# Sensact_v4_2.net
KiCad netlist of a schematic drawn in EAGLE
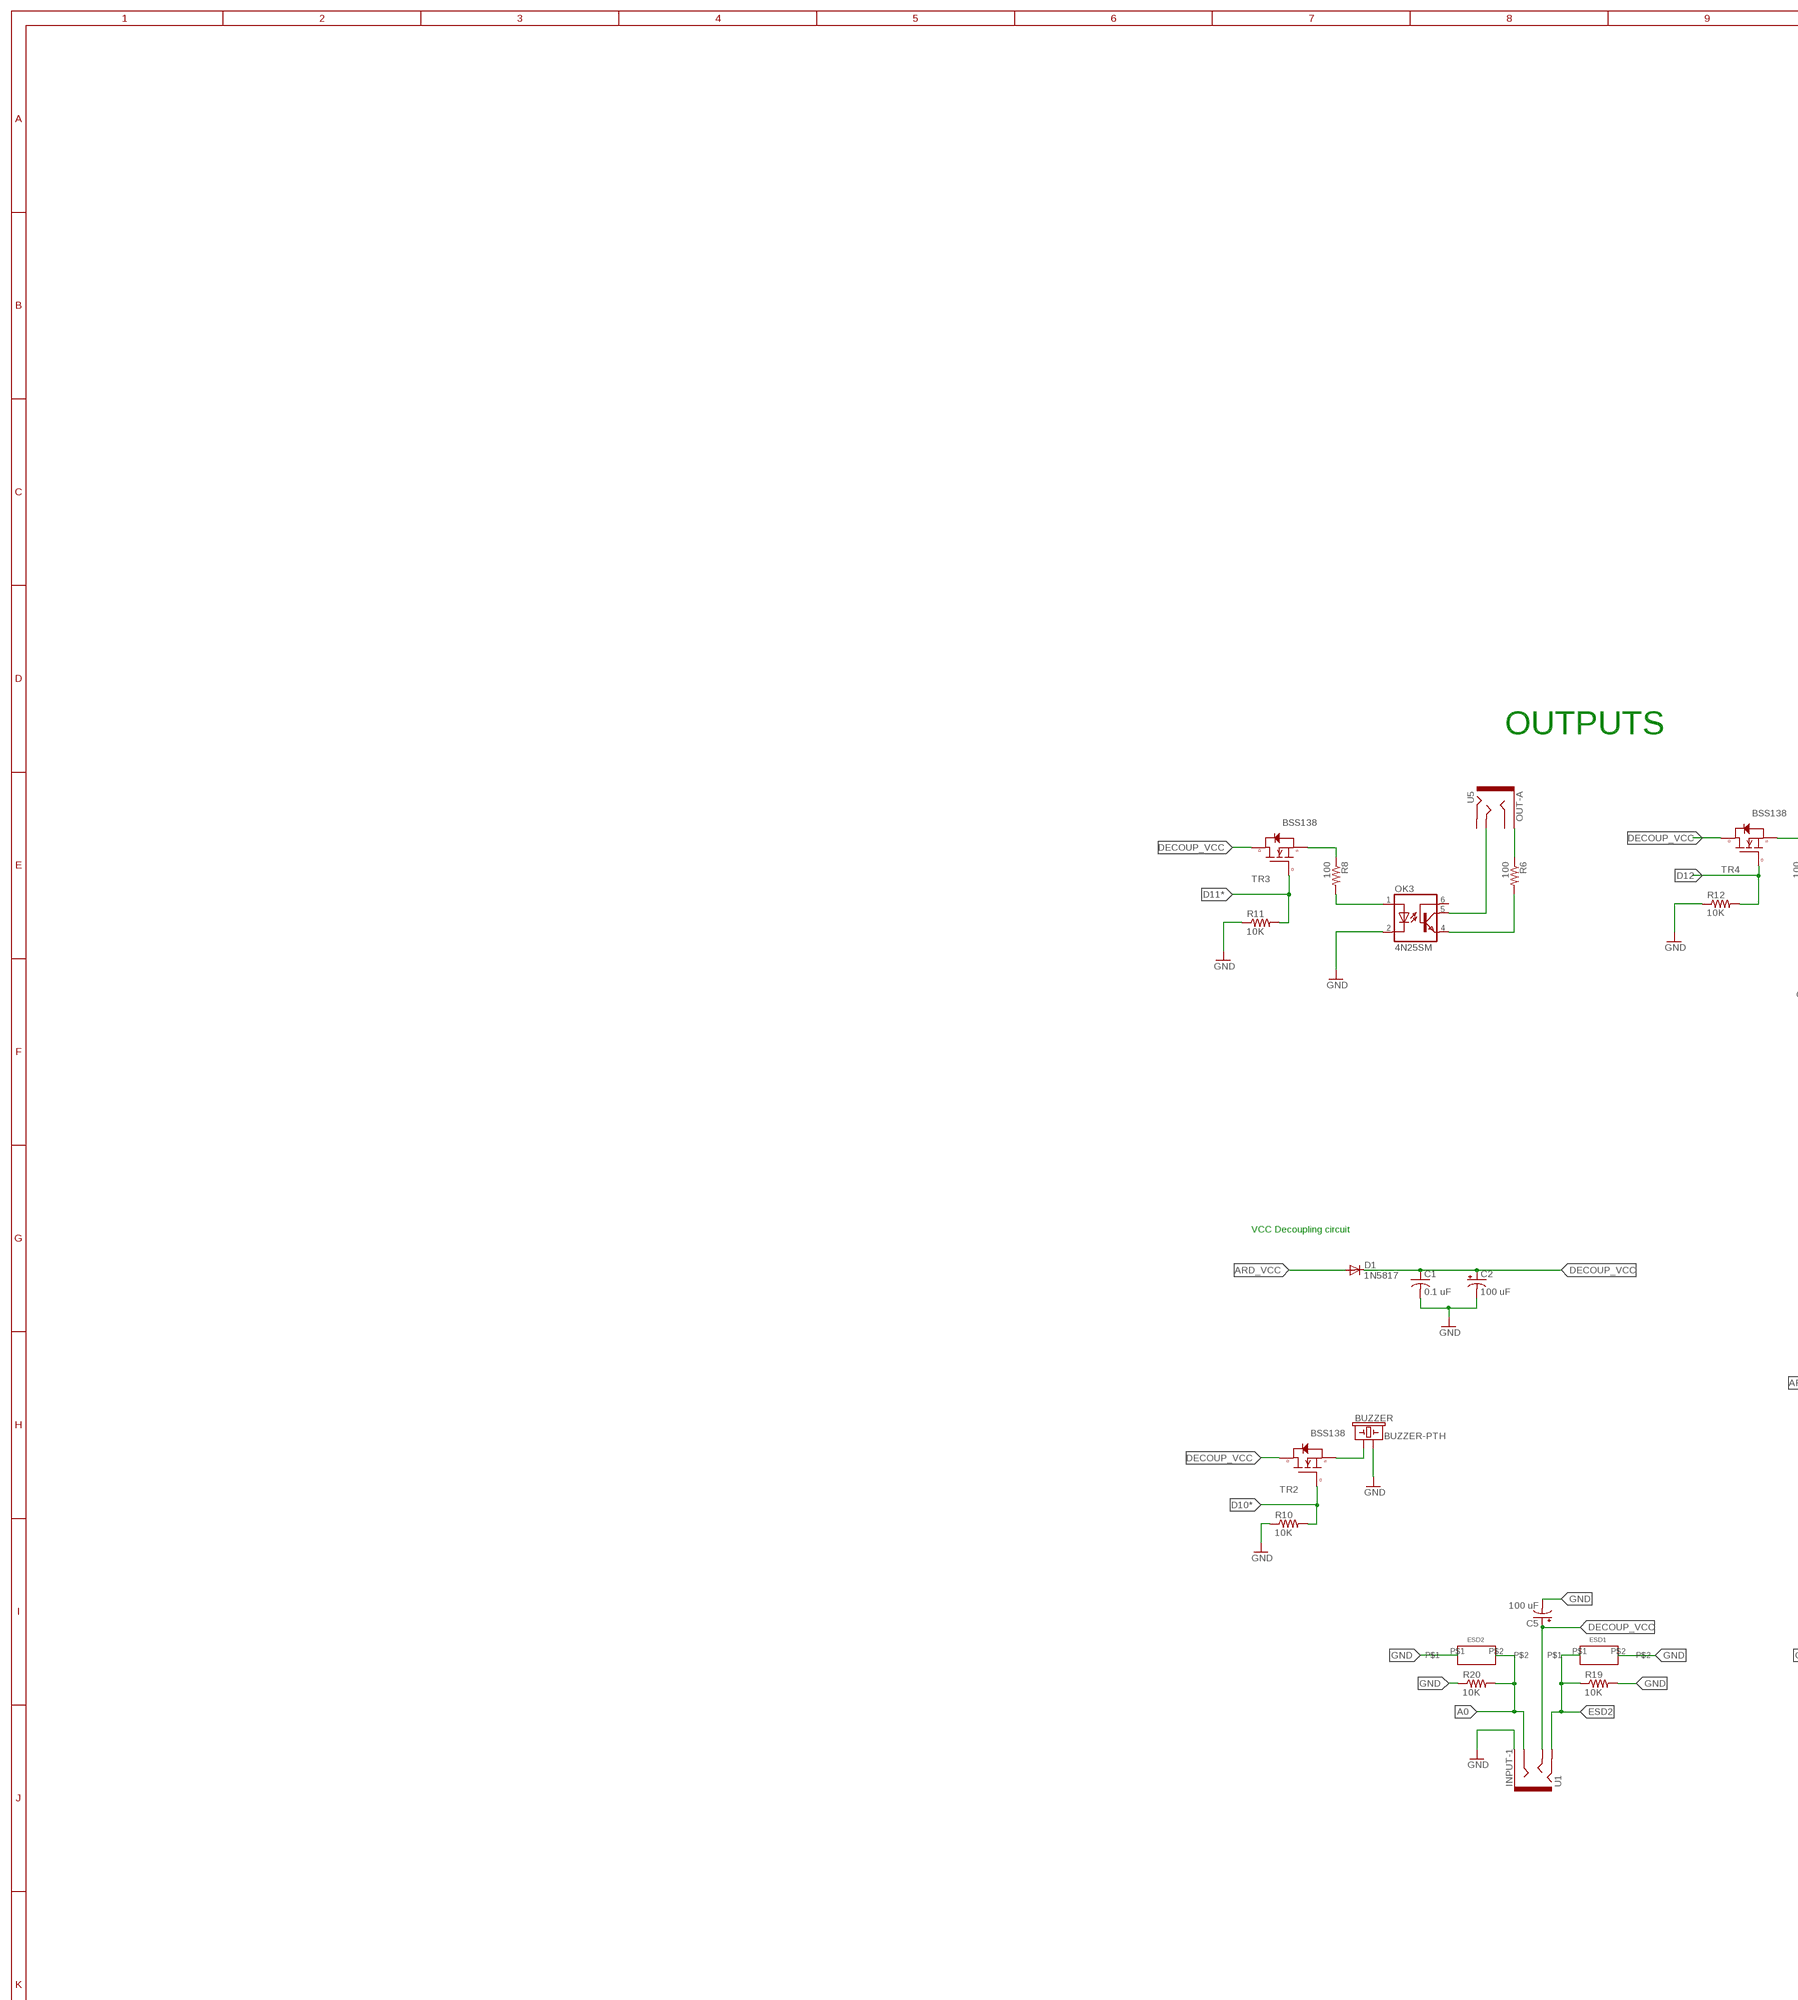
[diagram p0: schematic, sheet 1, part 1 of 3]
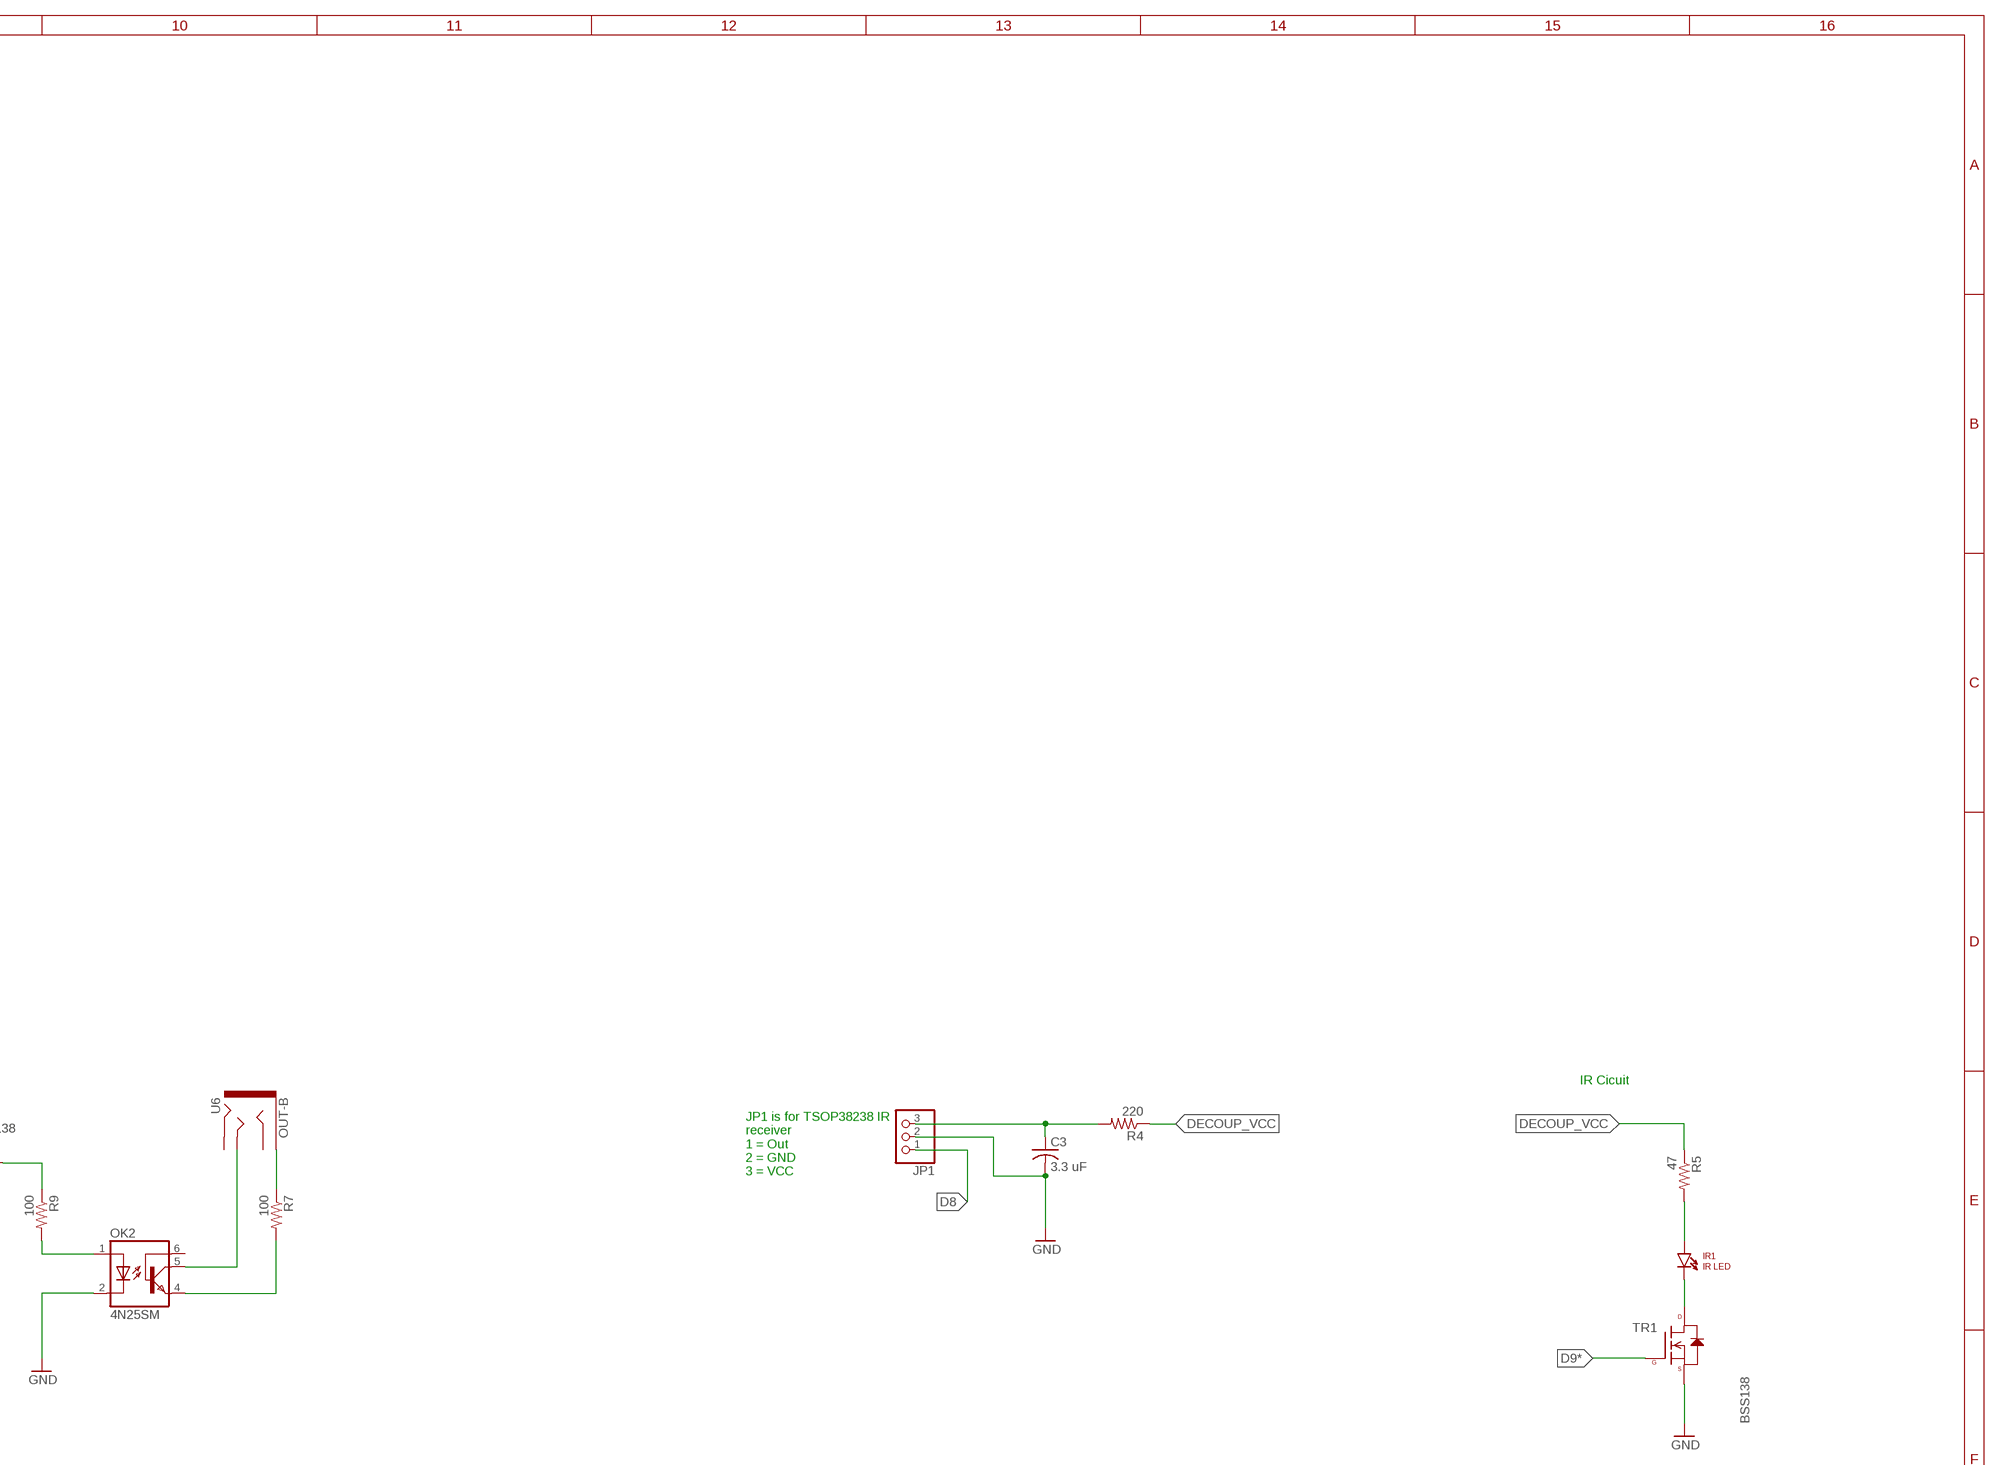
[diagram p1: schematic, sheet 1, part 2 of 3]
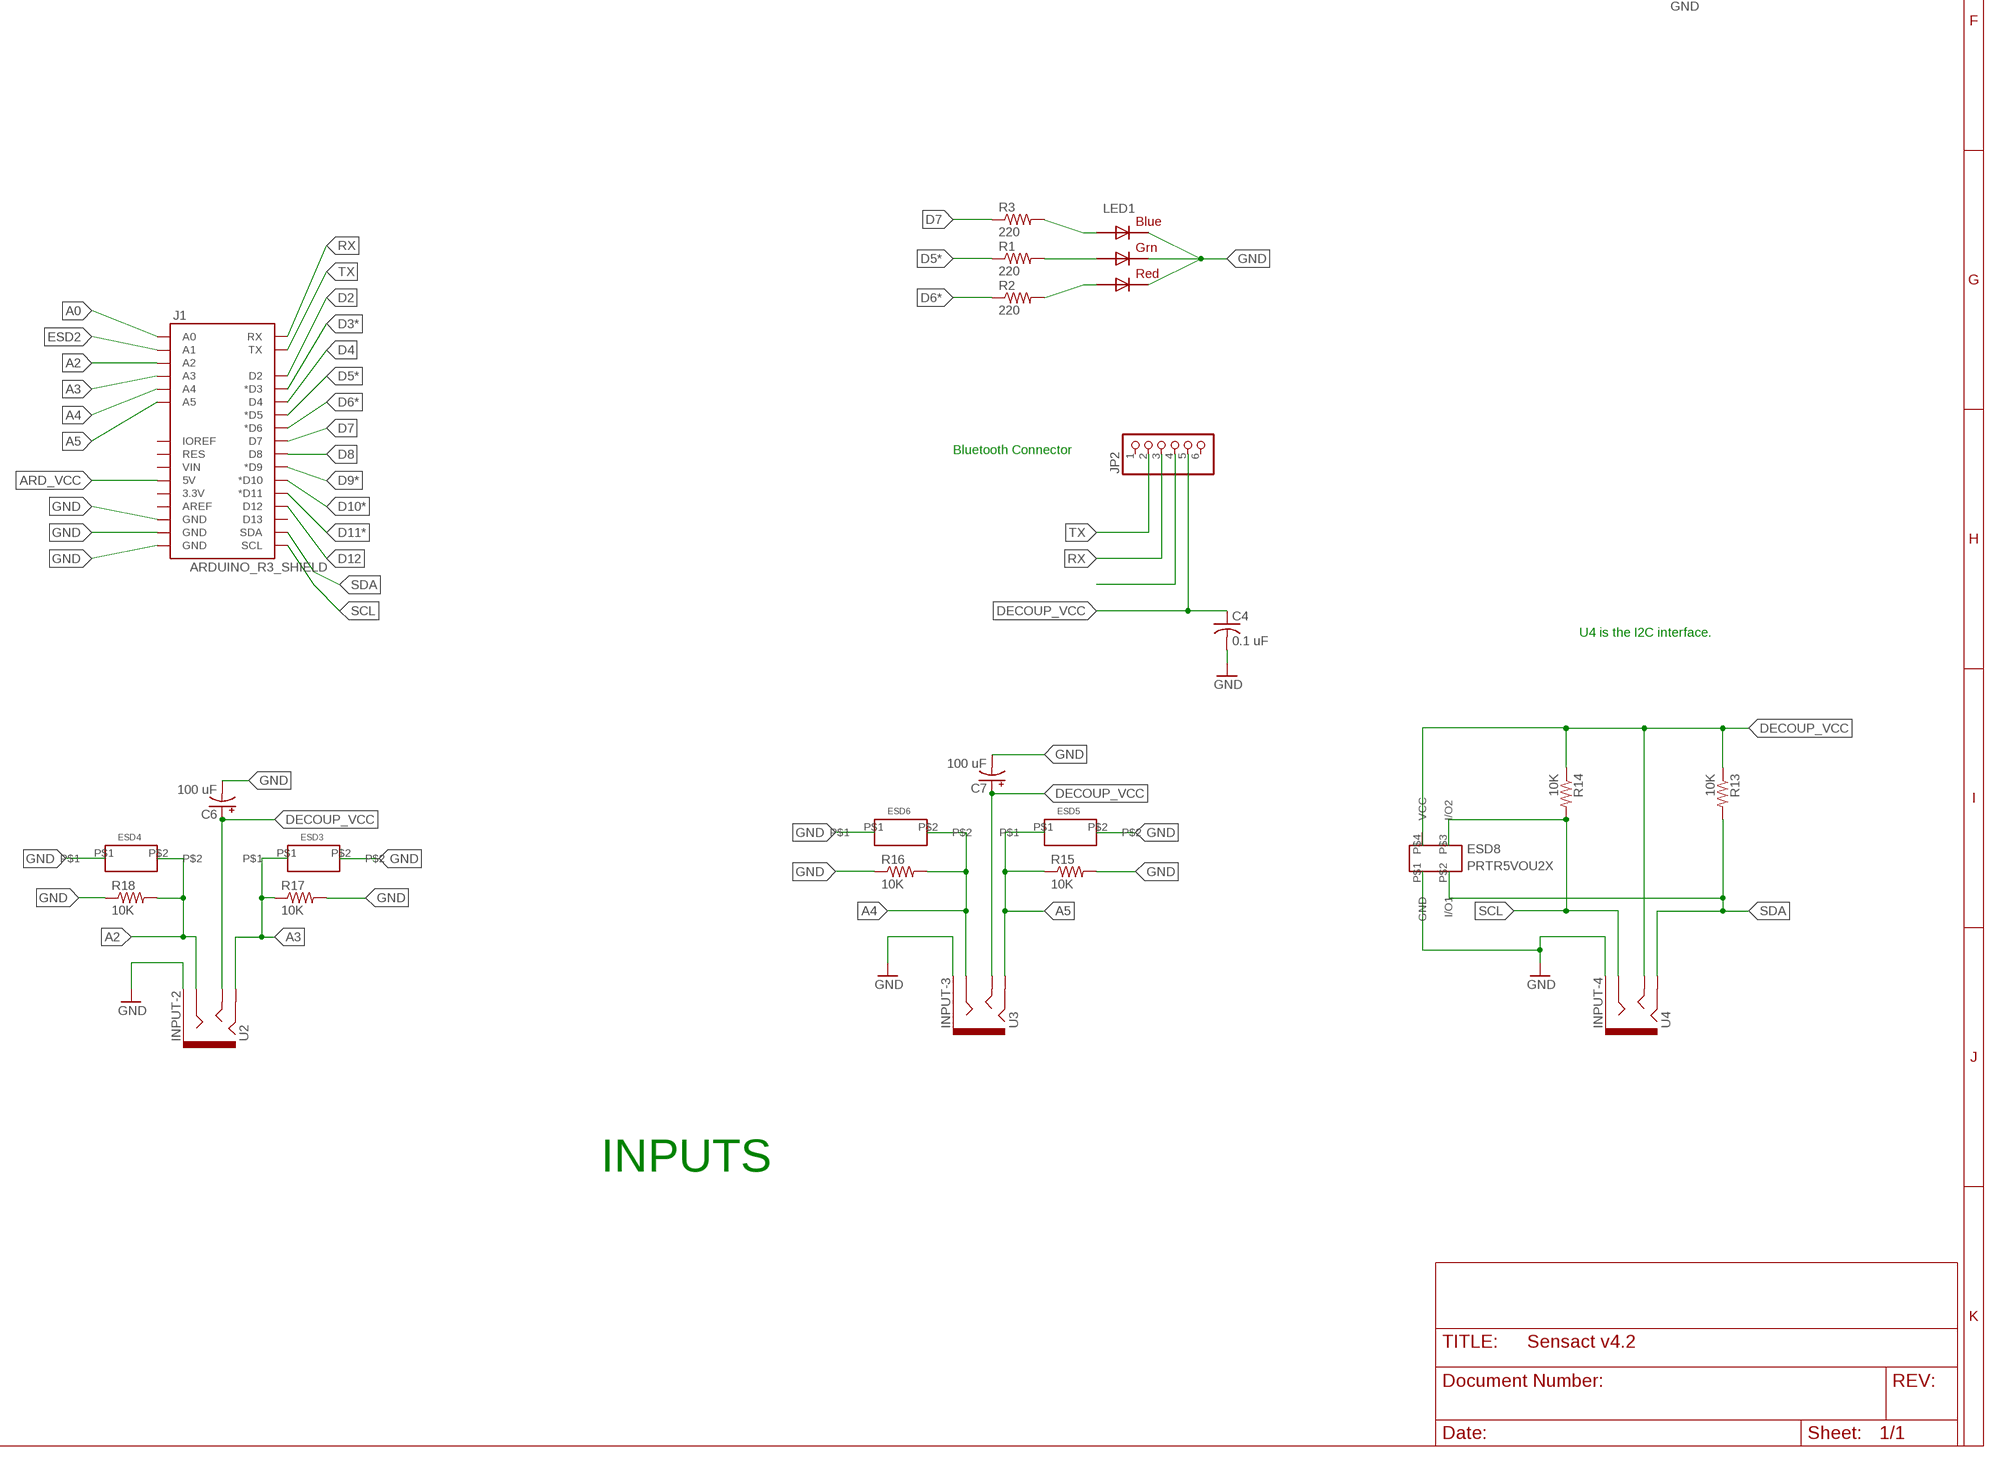
[diagram p2: schematic, sheet 1, part 3 of 3]

(export (version "E")
  (design (tool "Eeschema 10.0.6"))
  (components
    (comp (ref "BUZZER")
      (value "BUZZER-PTH")
      (footprint "eagle-import:BUZZER-12MM")
      (libsource (lib "eagle-import") (part "BUZZER-PTH"))
    )
    (comp (ref "C1")
      (value "0.1 uF")
      (footprint "eagle-import:C0805")
      (libsource (lib "eagle-import") (part "C-USC0805"))
    )
    (comp (ref "C2")
      (value "100 uF")
      (footprint "eagle-import:PANASONIC_C")
      (libsource (lib "eagle-import") (part "CAP_POLC"))
    )
    (comp (ref "C3")
      (value "3.3 uF")
      (footprint "eagle-import:C0805")
      (libsource (lib "eagle-import") (part "C-USC0805"))
    )
    (comp (ref "C4")
      (value "0.1 uF")
      (footprint "eagle-import:C0805")
      (libsource (lib "eagle-import") (part "C-USC0805"))
    )
    (comp (ref "C5")
      (value "100 uF")
      (footprint "eagle-import:PANASONIC_C")
      (libsource (lib "eagle-import") (part "CAP_POLC"))
    )
    (comp (ref "C6")
      (value "100 uF")
      (footprint "eagle-import:PANASONIC_C")
      (libsource (lib "eagle-import") (part "CAP_POLC"))
    )
    (comp (ref "C7")
      (value "100 uF")
      (footprint "eagle-import:PANASONIC_C")
      (libsource (lib "eagle-import") (part "CAP_POLC"))
    )
    (comp (ref "D1")
      (value "1N5817")
      (footprint "eagle-import:DO214AC")
      (libsource (lib "eagle-import") (part "DIODE-DO214AC"))
    )
    (comp (ref "ESD1")
      (value "PESD5V0S1BA")
      (footprint "eagle-import:SOD323")
      (libsource (lib "eagle-import") (part "PESD5V0S1BA"))
    )
    (comp (ref "ESD2")
      (value "PESD5V0S1BA")
      (footprint "eagle-import:SOD323")
      (libsource (lib "eagle-import") (part "PESD5V0S1BA"))
    )
    (comp (ref "ESD3")
      (value "PESD5V0S1BA")
      (footprint "eagle-import:SOD323")
      (libsource (lib "eagle-import") (part "PESD5V0S1BA"))
    )
    (comp (ref "ESD4")
      (value "PESD5V0S1BA")
      (footprint "eagle-import:SOD323")
      (libsource (lib "eagle-import") (part "PESD5V0S1BA"))
    )
    (comp (ref "ESD5")
      (value "PESD5V0S1BA")
      (footprint "eagle-import:SOD323")
      (libsource (lib "eagle-import") (part "PESD5V0S1BA"))
    )
    (comp (ref "ESD6")
      (value "PESD5V0S1BA")
      (footprint "eagle-import:SOD323")
      (libsource (lib "eagle-import") (part "PESD5V0S1BA"))
    )
    (comp (ref "ESD8")
      (value "PRTR5VOU2X")
      (footprint "eagle-import:215")
      (libsource (lib "eagle-import") (part "PRTR5VOU2X"))
    )
    (comp (ref "INPUT-1")
      (value "U1")
      (footprint "eagle-import:AUDIO-JACK-TRRS-THRUHOLE")
      (libsource (lib "eagle-import") (part "AUDIO-JACK-TRRS-THRUHOLE"))
    )
    (comp (ref "INPUT-2")
      (value "U2")
      (footprint "eagle-import:AUDIO-JACK-TRRS-THRUHOLE")
      (libsource (lib "eagle-import") (part "AUDIO-JACK-TRRS-THRUHOLE"))
    )
    (comp (ref "INPUT-3")
      (value "U3")
      (footprint "eagle-import:AUDIO-JACK-TRRS-THRUHOLE")
      (libsource (lib "eagle-import") (part "AUDIO-JACK-TRRS-THRUHOLE"))
    )
    (comp (ref "INPUT-4")
      (value "U4")
      (footprint "eagle-import:AUDIO-JACK-TRRS-THRUHOLE")
      (libsource (lib "eagle-import") (part "AUDIO-JACK-TRRS-THRUHOLE"))
    )
    (comp (ref "IR1")
      (value "IR LED")
      (footprint "eagle-import:LTE-302")
      (libsource (lib "eagle-import") (part "LTE-302"))
    )
    (comp (ref "J1")
      (value "ARDUINO_R3_SHIELD")
      (footprint "eagle-import:UNO_R3_SHIELD")
      (libsource (lib "eagle-import") (part "ARDUINO_R3_SHIELD"))
    )
    (comp (ref "JP1")
      (value "PINHD-1X3")
      (footprint "eagle-import:1X03")
      (libsource (lib "eagle-import") (part "PINHD-1X3"))
    )
    (comp (ref "JP2")
      (value "PINHD-1X6")
      (footprint "eagle-import:1X06")
      (libsource (lib "eagle-import") (part "PINHD-1X6"))
    )
    (comp (ref "LED1")
      (value "RGBLED5050")
      (footprint "eagle-import:RGBLED5050")
      (libsource (lib "eagle-import") (part "RGBLED5050"))
    )
    (comp (ref "OK2")
      (value "4N25SM")
      (footprint "eagle-import:DIL6-SMD")
      (fields (field (name "MF") "FAIRCHILD SEMICONDUCTOR"))
      (libsource (lib "eagle-import") (part "4N?MS25"))
    )
    (comp (ref "OK3")
      (value "4N25SM")
      (footprint "eagle-import:DIL6-SMD")
      (fields (field (name "MF") "FAIRCHILD SEMICONDUCTOR"))
      (libsource (lib "eagle-import") (part "4N?MS25"))
    )
    (comp (ref "OUT-A")
      (value "U5")
      (footprint "eagle-import:AUDIO-JACK-TRRS-THRUHOLE")
      (libsource (lib "eagle-import") (part "AUDIO-JACK-TRRS-THRUHOLE"))
    )
    (comp (ref "OUT-B")
      (value "U6")
      (footprint "eagle-import:AUDIO-JACK-TRRS-THRUHOLE")
      (libsource (lib "eagle-import") (part "AUDIO-JACK-TRRS-THRUHOLE"))
    )
    (comp (ref "R1")
      (value "220")
      (footprint "eagle-import:0805")
      (libsource (lib "eagle-import") (part "RESISTOR0805-RES"))
    )
    (comp (ref "R2")
      (value "220")
      (footprint "eagle-import:0805")
      (libsource (lib "eagle-import") (part "RESISTOR0805-RES"))
    )
    (comp (ref "R3")
      (value "220")
      (footprint "eagle-import:0805")
      (libsource (lib "eagle-import") (part "RESISTOR0805-RES"))
    )
    (comp (ref "R4")
      (value "220")
      (footprint "eagle-import:0805")
      (libsource (lib "eagle-import") (part "RESISTOR0805-RES"))
    )
    (comp (ref "R5")
      (value "47")
      (footprint "eagle-import:0805")
      (libsource (lib "eagle-import") (part "RESISTOR0805-RES"))
    )
    (comp (ref "R6")
      (value "100")
      (footprint "eagle-import:0805")
      (libsource (lib "eagle-import") (part "RESISTOR0805-RES"))
    )
    (comp (ref "R7")
      (value "100")
      (footprint "eagle-import:0805")
      (libsource (lib "eagle-import") (part "RESISTOR0805-RES"))
    )
    (comp (ref "R8")
      (value "100")
      (footprint "eagle-import:0805")
      (libsource (lib "eagle-import") (part "RESISTOR0805-RES"))
    )
    (comp (ref "R9")
      (value "100")
      (footprint "eagle-import:0805")
      (libsource (lib "eagle-import") (part "RESISTOR0805-RES"))
    )
    (comp (ref "R10")
      (value "10K")
      (footprint "eagle-import:0805")
      (libsource (lib "eagle-import") (part "RESISTOR0805-RES"))
    )
    (comp (ref "R11")
      (value "10K")
      (footprint "eagle-import:0805")
      (libsource (lib "eagle-import") (part "RESISTOR0805-RES"))
    )
    (comp (ref "R12")
      (value "10K")
      (footprint "eagle-import:0805")
      (libsource (lib "eagle-import") (part "RESISTOR0805-RES"))
    )
    (comp (ref "R13")
      (value "10K")
      (footprint "eagle-import:0805")
      (libsource (lib "eagle-import") (part "RESISTOR0805-RES"))
    )
    (comp (ref "R14")
      (value "10K")
      (footprint "eagle-import:0805")
      (libsource (lib "eagle-import") (part "RESISTOR0805-RES"))
    )
    (comp (ref "R15")
      (value "10K")
      (footprint "eagle-import:0805")
      (libsource (lib "eagle-import") (part "RESISTOR0805-RES"))
    )
    (comp (ref "R16")
      (value "10K")
      (footprint "eagle-import:0805")
      (libsource (lib "eagle-import") (part "RESISTOR0805-RES"))
    )
    (comp (ref "R17")
      (value "10K")
      (footprint "eagle-import:0805")
      (libsource (lib "eagle-import") (part "RESISTOR0805-RES"))
    )
    (comp (ref "R18")
      (value "10K")
      (footprint "eagle-import:0805")
      (libsource (lib "eagle-import") (part "RESISTOR0805-RES"))
    )
    (comp (ref "R19")
      (value "10K")
      (footprint "eagle-import:0805")
      (libsource (lib "eagle-import") (part "RESISTOR0805-RES"))
    )
    (comp (ref "R20")
      (value "10K")
      (footprint "eagle-import:0805")
      (libsource (lib "eagle-import") (part "RESISTOR0805-RES"))
    )
    (comp (ref "TR1")
      (value "BSS138")
      (footprint "eagle-import:SOT23-3")
      (libsource (lib "eagle-import") (part "N-CHANNEL-MOSFET-BSS138"))
    )
    (comp (ref "TR2")
      (value "BSS138")
      (footprint "eagle-import:SOT23-3")
      (libsource (lib "eagle-import") (part "N-CHANNEL-MOSFET-BSS138"))
    )
    (comp (ref "TR3")
      (value "BSS138")
      (footprint "eagle-import:SOT23-3")
      (libsource (lib "eagle-import") (part "N-CHANNEL-MOSFET-BSS138"))
    )
    (comp (ref "TR4")
      (value "BSS138")
      (footprint "eagle-import:SOT23-3")
      (libsource (lib "eagle-import") (part "N-CHANNEL-MOSFET-BSS138"))
    )
  )
  (nets
    (net (code "1") (name "A0") (class "Default")
      (node (ref "ESD2") (pin "P$2") (pinfunction "P$2_P$2") (pintype "bidirectional"))
      (node (ref "INPUT-1") (pin "RING1") (pinfunction "RING1_RING1") (pintype "bidirectional"))
      (node (ref "J1") (pin "A0") (pinfunction "A0_A0") (pintype "bidirectional"))
      (node (ref "R20") (pin "2") (pinfunction "2_2") (pintype "passive"))
    )
    (net (code "2") (name "A2") (class "Default")
      (node (ref "ESD4") (pin "P$2") (pinfunction "P$2_P$2") (pintype "bidirectional"))
      (node (ref "INPUT-2") (pin "RING1") (pinfunction "RING1_RING1") (pintype "bidirectional"))
      (node (ref "J1") (pin "A2") (pinfunction "A2_A2") (pintype "bidirectional"))
      (node (ref "R18") (pin "2") (pinfunction "2_2") (pintype "passive"))
    )
    (net (code "3") (name "A3") (class "Default")
      (node (ref "ESD3") (pin "P$1") (pinfunction "P$1_P$1") (pintype "bidirectional"))
      (node (ref "INPUT-2") (pin "RING2") (pinfunction "RING2_RING2") (pintype "bidirectional"))
      (node (ref "J1") (pin "A3") (pinfunction "A3_A3") (pintype "bidirectional"))
      (node (ref "R17") (pin "1") (pinfunction "1_1") (pintype "passive"))
    )
    (net (code "4") (name "A4") (class "Default")
      (node (ref "ESD6") (pin "P$2") (pinfunction "P$2_P$2") (pintype "bidirectional"))
      (node (ref "INPUT-3") (pin "RING1") (pinfunction "RING1_RING1") (pintype "bidirectional"))
      (node (ref "J1") (pin "A4") (pinfunction "A4_A4") (pintype "bidirectional"))
      (node (ref "R16") (pin "2") (pinfunction "2_2") (pintype "passive"))
    )
    (net (code "5") (name "A5") (class "Default")
      (node (ref "ESD5") (pin "P$1") (pinfunction "P$1_P$1") (pintype "bidirectional"))
      (node (ref "INPUT-3") (pin "RING2") (pinfunction "RING2_RING2") (pintype "bidirectional"))
      (node (ref "J1") (pin "A5") (pinfunction "A5_A5") (pintype "bidirectional"))
      (node (ref "R15") (pin "1") (pinfunction "1_1") (pintype "passive"))
    )
    (net (code "6") (name "ARD_VCC") (class "Default")
      (node (ref "D1") (pin "A") (pinfunction "A_A") (pintype "passive"))
      (node (ref "J1") (pin "5V") (pinfunction "5V_5V") (pintype "bidirectional"))
    )
    (net (code "7") (name "D2") (class "Default")
      (node (ref "J1") (pin "D2") (pinfunction "D2_D2") (pintype "bidirectional"))
    )
    (net (code "8") (name "D3*") (class "Default")
      (node (ref "J1") (pin "D3") (pinfunction "*D3_D3") (pintype "bidirectional"))
    )
    (net (code "9") (name "D4") (class "Default")
      (node (ref "J1") (pin "D4") (pinfunction "D4_D4") (pintype "bidirectional"))
    )
    (net (code "10") (name "D5*") (class "Default")
      (node (ref "J1") (pin "D5") (pinfunction "*D5_D5") (pintype "bidirectional"))
      (node (ref "R1") (pin "1") (pinfunction "1_1") (pintype "passive"))
    )
    (net (code "11") (name "D6*") (class "Default")
      (node (ref "J1") (pin "D6") (pinfunction "*D6_D6") (pintype "bidirectional"))
      (node (ref "R2") (pin "1") (pinfunction "1_1") (pintype "passive"))
    )
    (net (code "12") (name "D7") (class "Default")
      (node (ref "J1") (pin "D7") (pinfunction "D7_D7") (pintype "bidirectional"))
      (node (ref "R3") (pin "1") (pinfunction "1_1") (pintype "passive"))
    )
    (net (code "13") (name "D8") (class "Default")
      (node (ref "J1") (pin "D8") (pinfunction "D8_D8") (pintype "bidirectional"))
      (node (ref "JP1") (pin "1") (pinfunction "1_1") (pintype "passive"))
    )
    (net (code "14") (name "D9*") (class "Default")
      (node (ref "J1") (pin "D9") (pinfunction "*D9_D9") (pintype "bidirectional"))
      (node (ref "TR1") (pin "1") (pinfunction "G_1") (pintype "passive"))
    )
    (net (code "15") (name "D10*") (class "Default")
      (node (ref "J1") (pin "D10") (pinfunction "*D10_D10") (pintype "bidirectional"))
      (node (ref "R10") (pin "2") (pinfunction "2_2") (pintype "passive"))
      (node (ref "TR2") (pin "1") (pinfunction "G_1") (pintype "passive"))
    )
    (net (code "16") (name "D11*") (class "Default")
      (node (ref "J1") (pin "D11") (pinfunction "*D11_D11") (pintype "bidirectional"))
      (node (ref "R11") (pin "2") (pinfunction "2_2") (pintype "passive"))
      (node (ref "TR3") (pin "1") (pinfunction "G_1") (pintype "passive"))
    )
    (net (code "17") (name "D12") (class "Default")
      (node (ref "J1") (pin "D12") (pinfunction "D12_D12") (pintype "bidirectional"))
      (node (ref "R12") (pin "2") (pinfunction "2_2") (pintype "passive"))
      (node (ref "TR4") (pin "1") (pinfunction "G_1") (pintype "passive"))
    )
    (net (code "18") (name "DECOUP_VCC") (class "Default")
      (node (ref "C1") (pin "1") (pinfunction "1_1") (pintype "passive"))
      (node (ref "C2") (pin "+") (pinfunction "+_+") (pintype "passive"))
      (node (ref "C4") (pin "1") (pinfunction "1_1") (pintype "passive"))
      (node (ref "C5") (pin "+") (pinfunction "+_+") (pintype "passive"))
      (node (ref "C6") (pin "+") (pinfunction "+_+") (pintype "passive"))
      (node (ref "C7") (pin "+") (pinfunction "+_+") (pintype "passive"))
      (node (ref "D1") (pin "C") (pinfunction "C_C") (pintype "passive"))
      (node (ref "ESD8") (pin "P$4") (pinfunction "VCC_P$4") (pintype "bidirectional"))
      (node (ref "INPUT-1") (pin "TIP") (pinfunction "TIP_TIP") (pintype "bidirectional"))
      (node (ref "INPUT-2") (pin "TIP") (pinfunction "TIP_TIP") (pintype "bidirectional"))
      (node (ref "INPUT-3") (pin "TIP") (pinfunction "TIP_TIP") (pintype "bidirectional"))
      (node (ref "INPUT-4") (pin "TIP") (pinfunction "TIP_TIP") (pintype "bidirectional"))
      (node (ref "JP2") (pin "5") (pinfunction "5_5") (pintype "passive"))
      (node (ref "R13") (pin "1") (pinfunction "1_1") (pintype "passive"))
      (node (ref "R14") (pin "1") (pinfunction "1_1") (pintype "passive"))
      (node (ref "R4") (pin "1") (pinfunction "1_1") (pintype "passive"))
      (node (ref "R5") (pin "1") (pinfunction "1_1") (pintype "passive"))
      (node (ref "TR2") (pin "3") (pinfunction "D_3") (pintype "passive"))
      (node (ref "TR3") (pin "3") (pinfunction "D_3") (pintype "passive"))
      (node (ref "TR4") (pin "3") (pinfunction "D_3") (pintype "passive"))
    )
    (net (code "19") (name "ESD2") (class "Default")
      (node (ref "ESD1") (pin "P$1") (pinfunction "P$1_P$1") (pintype "bidirectional"))
      (node (ref "INPUT-1") (pin "RING2") (pinfunction "RING2_RING2") (pintype "bidirectional"))
      (node (ref "J1") (pin "A1") (pinfunction "A1_A1") (pintype "bidirectional"))
      (node (ref "R19") (pin "1") (pinfunction "1_1") (pintype "passive"))
    )
    (net (code "20") (name "GND") (class "Default")
      (node (ref "BUZZER") (pin "-") (pinfunction "2_-") (pintype "passive"))
      (node (ref "C1") (pin "2") (pinfunction "2_2") (pintype "passive"))
      (node (ref "C2") (pin "-") (pinfunction "-_-") (pintype "passive"))
      (node (ref "C3") (pin "2") (pinfunction "2_2") (pintype "passive"))
      (node (ref "C4") (pin "2") (pinfunction "2_2") (pintype "passive"))
      (node (ref "ESD1") (pin "P$2") (pinfunction "P$2_P$2") (pintype "bidirectional"))
      (node (ref "ESD2") (pin "P$1") (pinfunction "P$1_P$1") (pintype "bidirectional"))
      (node (ref "ESD3") (pin "P$2") (pinfunction "P$2_P$2") (pintype "bidirectional"))
      (node (ref "ESD4") (pin "P$1") (pinfunction "P$1_P$1") (pintype "bidirectional"))
      (node (ref "ESD5") (pin "P$2") (pinfunction "P$2_P$2") (pintype "bidirectional"))
      (node (ref "ESD6") (pin "P$1") (pinfunction "P$1_P$1") (pintype "bidirectional"))
      (node (ref "ESD8") (pin "P$1") (pinfunction "GND_P$1") (pintype "bidirectional"))
      (node (ref "INPUT-1") (pin "SLEEVE") (pinfunction "EARTH_SLEEVE") (pintype "bidirectional"))
      (node (ref "INPUT-2") (pin "SLEEVE") (pinfunction "EARTH_SLEEVE") (pintype "bidirectional"))
      (node (ref "INPUT-3") (pin "SLEEVE") (pinfunction "EARTH_SLEEVE") (pintype "bidirectional"))
      (node (ref "INPUT-4") (pin "SLEEVE") (pinfunction "EARTH_SLEEVE") (pintype "bidirectional"))
      (node (ref "J1") (pin "GND@0") (pinfunction "GND_GND@0") (pintype "bidirectional"))
      (node (ref "J1") (pin "GND@1") (pinfunction "GND_GND@1") (pintype "bidirectional"))
      (node (ref "J1") (pin "GND@2") (pinfunction "GND_GND@2") (pintype "bidirectional"))
      (node (ref "JP1") (pin "2") (pinfunction "2_2") (pintype "passive"))
      (node (ref "JP2") (pin "4") (pinfunction "4_4") (pintype "passive"))
      (node (ref "LED1") (pin "4") (pinfunction "BLUE_C_4") (pintype "bidirectional"))
      (node (ref "LED1") (pin "5") (pinfunction "RED_C_5") (pintype "bidirectional"))
      (node (ref "LED1") (pin "6") (pinfunction "GREEN_C_6") (pintype "bidirectional"))
      (node (ref "OK2") (pin "2") (pinfunction "C_2") (pintype "passive"))
      (node (ref "OK3") (pin "2") (pinfunction "C_2") (pintype "passive"))
      (node (ref "R10") (pin "1") (pinfunction "1_1") (pintype "passive"))
      (node (ref "R11") (pin "1") (pinfunction "1_1") (pintype "passive"))
      (node (ref "R12") (pin "1") (pinfunction "1_1") (pintype "passive"))
      (node (ref "R15") (pin "2") (pinfunction "2_2") (pintype "passive"))
      (node (ref "R16") (pin "1") (pinfunction "1_1") (pintype "passive"))
      (node (ref "R17") (pin "2") (pinfunction "2_2") (pintype "passive"))
      (node (ref "R18") (pin "1") (pinfunction "1_1") (pintype "passive"))
      (node (ref "R19") (pin "2") (pinfunction "2_2") (pintype "passive"))
      (node (ref "R20") (pin "1") (pinfunction "1_1") (pintype "passive"))
      (node (ref "TR1") (pin "2") (pinfunction "S_2") (pintype "passive"))
    )
    (net (code "21") (name "Net-(BUZZER-1)") (class "Default")
      (node (ref "BUZZER") (pin "+") (pinfunction "1_+") (pintype "passive"))
      (node (ref "TR2") (pin "2") (pinfunction "S_2") (pintype "passive"))
    )
    (net (code "22") (name "Net-(C3-Pad1)") (class "Default")
      (node (ref "C3") (pin "1") (pinfunction "1_1") (pintype "passive"))
      (node (ref "JP1") (pin "3") (pinfunction "3_3") (pintype "passive"))
      (node (ref "R4") (pin "2") (pinfunction "2_2") (pintype "passive"))
    )
    (net (code "23") (name "Net-(IR1-PadA)") (class "Default")
      (node (ref "IR1") (pin "A") (pinfunction "A_A") (pintype "bidirectional"))
      (node (ref "R5") (pin "2") (pinfunction "2_2") (pintype "passive"))
    )
    (net (code "24") (name "Net-(LED1-BLUE_A)") (class "Default")
      (node (ref "LED1") (pin "3") (pinfunction "BLUE_A_3") (pintype "bidirectional"))
      (node (ref "R3") (pin "2") (pinfunction "2_2") (pintype "passive"))
    )
    (net (code "25") (name "Net-(LED1-GREEN_A)") (class "Default")
      (node (ref "LED1") (pin "1") (pinfunction "GREEN_A_1") (pintype "bidirectional"))
      (node (ref "R1") (pin "2") (pinfunction "2_2") (pintype "passive"))
    )
    (net (code "26") (name "Net-(LED1-RED_A)") (class "Default")
      (node (ref "LED1") (pin "2") (pinfunction "RED_A_2") (pintype "bidirectional"))
      (node (ref "R2") (pin "2") (pinfunction "2_2") (pintype "passive"))
    )
    (net (code "27") (name "Net-(OK2-A)") (class "Default")
      (node (ref "OK2") (pin "1") (pinfunction "A_1") (pintype "passive"))
      (node (ref "R9") (pin "2") (pinfunction "2_2") (pintype "passive"))
    )
    (net (code "28") (name "Net-(OK2-COL)") (class "Default")
      (node (ref "OK2") (pin "5") (pinfunction "COL_5") (pintype "passive"))
      (node (ref "OUT-B") (pin "TIP") (pinfunction "TIP_TIP") (pintype "bidirectional"))
    )
    (net (code "29") (name "Net-(OK2-EMI)") (class "Default")
      (node (ref "OK2") (pin "4") (pinfunction "EMI_4") (pintype "passive"))
      (node (ref "R7") (pin "2") (pinfunction "2_2") (pintype "passive"))
    )
    (net (code "30") (name "Net-(OK3-A)") (class "Default")
      (node (ref "OK3") (pin "1") (pinfunction "A_1") (pintype "passive"))
      (node (ref "R8") (pin "2") (pinfunction "2_2") (pintype "passive"))
    )
    (net (code "31") (name "Net-(OK3-COL)") (class "Default")
      (node (ref "OK3") (pin "5") (pinfunction "COL_5") (pintype "passive"))
      (node (ref "OUT-A") (pin "TIP") (pinfunction "TIP_TIP") (pintype "bidirectional"))
    )
    (net (code "32") (name "Net-(OK3-EMI)") (class "Default")
      (node (ref "OK3") (pin "4") (pinfunction "EMI_4") (pintype "passive"))
      (node (ref "R6") (pin "2") (pinfunction "2_2") (pintype "passive"))
    )
    (net (code "33") (name "Net-(OUT-A-EARTH)") (class "Default")
      (node (ref "OUT-A") (pin "SLEEVE") (pinfunction "EARTH_SLEEVE") (pintype "bidirectional"))
      (node (ref "R6") (pin "1") (pinfunction "1_1") (pintype "passive"))
    )
    (net (code "34") (name "Net-(OUT-B-EARTH)") (class "Default")
      (node (ref "OUT-B") (pin "SLEEVE") (pinfunction "EARTH_SLEEVE") (pintype "bidirectional"))
      (node (ref "R7") (pin "1") (pinfunction "1_1") (pintype "passive"))
    )
    (net (code "35") (name "Net-(TR1-D)") (class "Default")
      (node (ref "IR1") (pin "C") (pinfunction "C_C") (pintype "bidirectional"))
      (node (ref "TR1") (pin "3") (pinfunction "D_3") (pintype "passive"))
    )
    (net (code "36") (name "Net-(TR3-S)") (class "Default")
      (node (ref "R8") (pin "1") (pinfunction "1_1") (pintype "passive"))
      (node (ref "TR3") (pin "2") (pinfunction "S_2") (pintype "passive"))
    )
    (net (code "37") (name "Net-(TR4-S)") (class "Default")
      (node (ref "R9") (pin "1") (pinfunction "1_1") (pintype "passive"))
      (node (ref "TR4") (pin "2") (pinfunction "S_2") (pintype "passive"))
    )
    (net (code "38") (name "RX") (class "Default")
      (node (ref "J1") (pin "RX") (pinfunction "RX_RX") (pintype "bidirectional"))
      (node (ref "JP2") (pin "3") (pinfunction "3_3") (pintype "passive"))
    )
    (net (code "39") (name "SCL") (class "Default")
      (node (ref "ESD8") (pin "P$3") (pinfunction "I/O2_P$3") (pintype "bidirectional"))
      (node (ref "INPUT-4") (pin "RING1") (pinfunction "RING1_RING1") (pintype "bidirectional"))
      (node (ref "J1") (pin "SCL") (pinfunction "SCL_SCL") (pintype "bidirectional"))
      (node (ref "R14") (pin "2") (pinfunction "2_2") (pintype "passive"))
    )
    (net (code "40") (name "SDA") (class "Default")
      (node (ref "ESD8") (pin "P$2") (pinfunction "I/O1_P$2") (pintype "bidirectional"))
      (node (ref "INPUT-4") (pin "RING2") (pinfunction "RING2_RING2") (pintype "bidirectional"))
      (node (ref "J1") (pin "SDA") (pinfunction "SDA_SDA") (pintype "bidirectional"))
      (node (ref "R13") (pin "2") (pinfunction "2_2") (pintype "passive"))
    )
    (net (code "41") (name "TX") (class "Default")
      (node (ref "J1") (pin "TX") (pinfunction "TX_TX") (pintype "bidirectional"))
      (node (ref "JP2") (pin "2") (pinfunction "2_2") (pintype "passive"))
    )
    (net (code "42") (name "unconnected-(C5-Pad-)") (class "Default")
      (node (ref "C5") (pin "-") (pinfunction "-_-") (pintype "passive"))
    )
    (net (code "43") (name "unconnected-(C6-Pad-)") (class "Default")
      (node (ref "C6") (pin "-") (pinfunction "-_-") (pintype "passive"))
    )
    (net (code "44") (name "unconnected-(C7-Pad-)") (class "Default")
      (node (ref "C7") (pin "-") (pinfunction "-_-") (pintype "passive"))
    )
    (net (code "45") (name "unconnected-(J1-Pad3.3V)") (class "Default")
      (node (ref "J1") (pin "3.3V") (pinfunction "3.3V_3.3V") (pintype "bidirectional"))
    )
    (net (code "46") (name "unconnected-(J1-PadAREF)") (class "Default")
      (node (ref "J1") (pin "AREF") (pinfunction "AREF_AREF") (pintype "bidirectional"))
    )
    (net (code "47") (name "unconnected-(J1-PadD13)") (class "Default")
      (node (ref "J1") (pin "D13") (pinfunction "D13_D13") (pintype "bidirectional"))
    )
    (net (code "48") (name "unconnected-(J1-PadIOREF)") (class "Default")
      (node (ref "J1") (pin "IOREF") (pinfunction "IOREF_IOREF") (pintype "bidirectional"))
    )
    (net (code "49") (name "unconnected-(J1-PadRES)") (class "Default")
      (node (ref "J1") (pin "RES") (pinfunction "RES_RES") (pintype "bidirectional"))
    )
    (net (code "50") (name "unconnected-(J1-PadVIN)") (class "Default")
      (node (ref "J1") (pin "VIN") (pinfunction "VIN_VIN") (pintype "bidirectional"))
    )
    (net (code "51") (name "unconnected-(JP2-Pad1)") (class "Default")
      (node (ref "JP2") (pin "1") (pinfunction "1_1") (pintype "passive"))
    )
    (net (code "52") (name "unconnected-(JP2-Pad6)") (class "Default")
      (node (ref "JP2") (pin "6") (pinfunction "6_6") (pintype "passive"))
    )
    (net (code "53") (name "unconnected-(OK2-BAS-Pad6)") (class "Default")
      (node (ref "OK2") (pin "6") (pinfunction "BAS_6") (pintype "passive"))
    )
    (net (code "54") (name "unconnected-(OK3-BAS-Pad6)") (class "Default")
      (node (ref "OK3") (pin "6") (pinfunction "BAS_6") (pintype "passive"))
    )
    (net (code "55") (name "unconnected-(OUT-A-PadRING1)") (class "Default")
      (node (ref "OUT-A") (pin "RING1") (pinfunction "RING1_RING1") (pintype "bidirectional"))
    )
    (net (code "56") (name "unconnected-(OUT-A-PadRING2)") (class "Default")
      (node (ref "OUT-A") (pin "RING2") (pinfunction "RING2_RING2") (pintype "bidirectional"))
    )
    (net (code "57") (name "unconnected-(OUT-B-PadRING1)") (class "Default")
      (node (ref "OUT-B") (pin "RING1") (pinfunction "RING1_RING1") (pintype "bidirectional"))
    )
    (net (code "58") (name "unconnected-(OUT-B-PadRING2)") (class "Default")
      (node (ref "OUT-B") (pin "RING2") (pinfunction "RING2_RING2") (pintype "bidirectional"))
    )
  )
)
